# PLASMA.net
KiCad netlist of a schematic drawn in Altium Designer
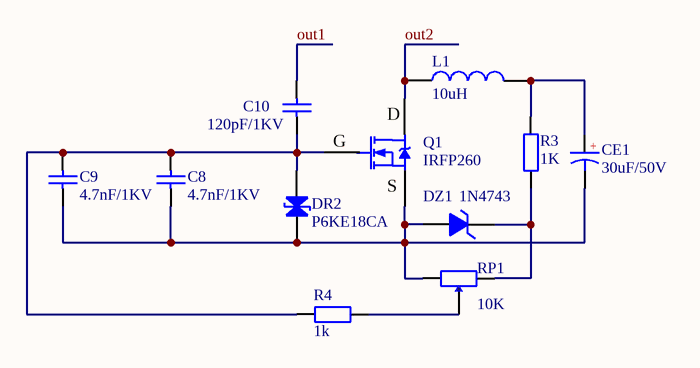
[diagram p0: PLASMA.SchDoc]

(export (version "E")
  (design (tool "Eeschema 10.0.6"))
  (components
    (comp (ref "C8")
      (value "4.7nF/1KV")
      (footprint "CY 7.5*10*4")
      (description "安规Y电容")
      (libsource (lib "0.1 - 电阻-电容-电感-保险丝-晶振-晶体-磁珠-电位器-法拉电容-馈通电容") (part "CY"))
    )
    (comp (ref "C9")
      (value "4.7nF/1KV")
      (footprint "CY 7.5*10*4")
      (description "安规Y电容")
      (libsource (lib "0.1 - 电阻-电容-电感-保险丝-晶振-晶体-磁珠-电位器-法拉电容-馈通电容") (part "CY"))
    )
    (comp (ref "C10")
      (value "120pF/1KV")
      (footprint "CY 7.5*10*4")
      (description "安规Y电容")
      (libsource (lib "0.1 - 电阻-电容-电感-保险丝-晶振-晶体-磁珠-电位器-法拉电容-馈通电容") (part "CY"))
    )
    (comp (ref "CE1")
      (value "30uF/50V")
      (footprint "CE-3.5*8")
      (description "直插电解电容")
      (libsource (lib "0.1 - 电阻-电容-电感-保险丝-晶振-晶体-磁珠-电位器-法拉电容-馈通电容") (part "CE"))
    )
    (comp (ref "DR2")
      (value "P6KE18CA")
      (footprint "DO-15")
      (description "瞬态电压抑制二极管")
      (libsource (lib "0.2 - 二极管-TVS-ESD-整流桥-放电管") (part "DR"))
    )
    (comp (ref "DZ1")
      (value "1N4743")
      (footprint "DO-41")
      (description "12V/1W稳压管")
      (libsource (lib "0.2 - 二极管-TVS-ESD-整流桥-放电管") (part "1N4742"))
    )
    (comp (ref "L1")
      (value "10uH")
      (footprint "AL0510")
      (description "色环电感")
      (libsource (lib "0.1 - 电阻-电容-电感-保险丝-晶振-晶体-磁珠-电位器-法拉电容-馈通电容") (part "L-AL"))
    )
    (comp (ref "Q1")
      (value "IRFP260")
      (footprint "TO247A")
      (description "N沟道 200V/30A")
      (libsource (lib "0.4 - 三极管-场效应管-可控硅") (part "IRFP250"))
    )
    (comp (ref "R3")
      (value "1K")
      (footprint "RS 2W")
      (description "直插色环电阻")
      (libsource (lib "0.1 - 电阻-电容-电感-保险丝-晶振-晶体-磁珠-电位器-法拉电容-馈通电容") (part "R-DIP"))
    )
    (comp (ref "R4")
      (value "1k")
      (footprint "RS 2W")
      (description "直插色环电阻")
      (libsource (lib "0.1 - 电阻-电容-电感-保险丝-晶振-晶体-磁珠-电位器-法拉电容-馈通电容") (part "R-DIP"))
    )
    (comp (ref "RP1")
      (value "10K")
      (footprint "3296W")
      (description "单联电位器")
      (libsource (lib "0.1 - 电阻-电容-电感-保险丝-晶振-晶体-磁珠-电位器-法拉电容-馈通电容") (part "RP"))
    )
  )
  (nets
    (net (code "1") (name "/out1") (class "Default")
      (node (ref "C10") (pin "2") (pinfunction "2_2") (pintype "passive"))
    )
    (net (code "2") (name "/out2") (class "Default")
      (node (ref "L1") (pin "1") (pinfunction "1_1") (pintype "passive"))
      (node (ref "Q1") (pin "2") (pinfunction "D_2") (pintype "passive"))
    )
    (net (code "3") (name "Net-(CE1-Pad1)") (class "Default")
      (node (ref "CE1") (pin "1") (pinfunction "1_1") (pintype "passive"))
      (node (ref "L1") (pin "2") (pinfunction "2_2") (pintype "passive"))
      (node (ref "R3") (pin "2") (pinfunction "2_2") (pintype "passive"))
    )
    (net (code "4") (name "Net-(DR2-A)") (class "Default")
      (node (ref "C10") (pin "1") (pinfunction "1_1") (pintype "passive"))
      (node (ref "C8") (pin "2") (pinfunction "2_2") (pintype "passive"))
      (node (ref "C9") (pin "2") (pinfunction "2_2") (pintype "passive"))
      (node (ref "DR2") (pin "1") (pinfunction "A_1") (pintype "passive"))
      (node (ref "Q1") (pin "1") (pinfunction "G_1") (pintype "passive"))
      (node (ref "R4") (pin "1") (pinfunction "1_1") (pintype "passive"))
    )
    (net (code "5") (name "Net-(DR2-K)") (class "Default")
      (node (ref "C8") (pin "1") (pinfunction "1_1") (pintype "passive"))
      (node (ref "C9") (pin "1") (pinfunction "1_1") (pintype "passive"))
      (node (ref "CE1") (pin "2") (pinfunction "2_2") (pintype "passive"))
      (node (ref "DR2") (pin "2") (pinfunction "K_2") (pintype "passive"))
      (node (ref "DZ1") (pin "1") (pinfunction "A_1") (pintype "passive"))
      (node (ref "Q1") (pin "3") (pinfunction "S_3") (pintype "passive"))
      (node (ref "RP1") (pin "3") (pinfunction "3_3") (pintype "passive"))
    )
    (net (code "6") (name "Net-(DZ1-K)") (class "Default")
      (node (ref "DZ1") (pin "2") (pinfunction "K_2") (pintype "passive"))
      (node (ref "R3") (pin "1") (pinfunction "1_1") (pintype "passive"))
      (node (ref "RP1") (pin "1") (pinfunction "1_1") (pintype "passive"))
    )
    (net (code "7") (name "Net-(R4-Pad2)") (class "Default")
      (node (ref "R4") (pin "2") (pinfunction "2_2") (pintype "passive"))
      (node (ref "RP1") (pin "2") (pinfunction "2_2") (pintype "passive"))
    )
  )
)
